# logger.net
KiCad netlist of a schematic drawn in EAGLE
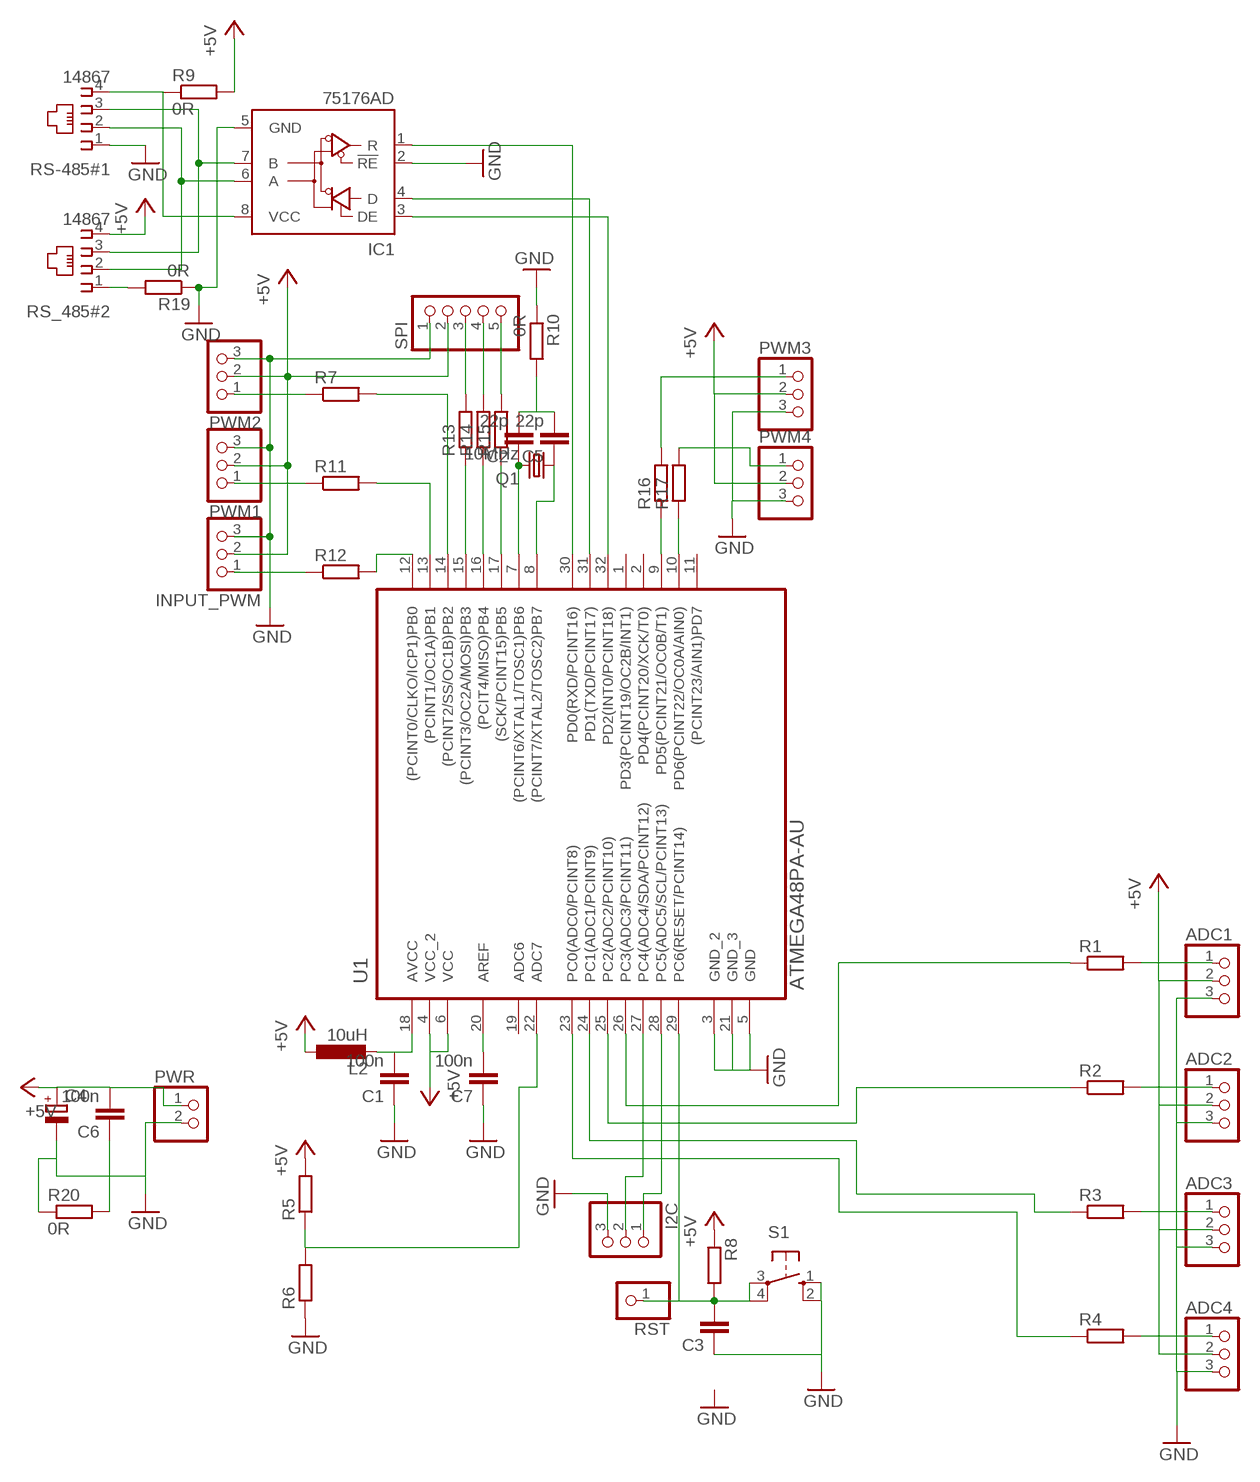
[diagram p0: schematic, sheet 1]

(export (version "E")
  (design (tool "Eeschema 10.0.6"))
  (components
    (comp (ref "ADC1")
      (value "PINHD-1X3")
      (footprint "eagle-import:1X03")
      (libsource (lib "eagle-import") (part "PINHD-1X3"))
    )
    (comp (ref "ADC2")
      (value "PINHD-1X3")
      (footprint "eagle-import:1X03")
      (libsource (lib "eagle-import") (part "PINHD-1X3"))
    )
    (comp (ref "ADC3")
      (value "PINHD-1X3")
      (footprint "eagle-import:1X03")
      (libsource (lib "eagle-import") (part "PINHD-1X3"))
    )
    (comp (ref "ADC4")
      (value "PINHD-1X3")
      (footprint "eagle-import:1X03")
      (libsource (lib "eagle-import") (part "PINHD-1X3"))
    )
    (comp (ref "C1")
      (value "100n")
      (footprint "eagle-import:C0805")
      (libsource (lib "eagle-import") (part "C-EUC0805"))
    )
    (comp (ref "C2")
      (value "22p")
      (footprint "eagle-import:C0805")
      (libsource (lib "eagle-import") (part "C-EUC0805"))
    )
    (comp (ref "C3")
      (value "C-EUC0805")
      (footprint "eagle-import:C0805")
      (libsource (lib "eagle-import") (part "C-EUC0805"))
    )
    (comp (ref "C4")
      (value "CPOL-EUE2,5-6E")
      (footprint "eagle-import:E2,5-6E")
      (libsource (lib "eagle-import") (part "CPOL-EUE2,5-6E"))
    )
    (comp (ref "C5")
      (value "22p")
      (footprint "eagle-import:C0805")
      (libsource (lib "eagle-import") (part "C-EUC0805"))
    )
    (comp (ref "C6")
      (value "100n")
      (footprint "eagle-import:C0805")
      (libsource (lib "eagle-import") (part "C-EUC0805"))
    )
    (comp (ref "C7")
      (value "100n")
      (footprint "eagle-import:C0805")
      (libsource (lib "eagle-import") (part "C-EUC0805"))
    )
    (comp (ref "I2C")
      (value "PINHD-1X3")
      (footprint "eagle-import:1X03")
      (libsource (lib "eagle-import") (part "PINHD-1X3"))
    )
    (comp (ref "IC1")
      (value "75176AD")
      (footprint "eagle-import:D_R-PDSO-G8")
      (libsource (lib "eagle-import") (part "75176AD"))
    )
    (comp (ref "INPUT_PWM")
      (value "PINHD-1X3")
      (footprint "eagle-import:1X03")
      (libsource (lib "eagle-import") (part "PINHD-1X3"))
    )
    (comp (ref "L2")
      (value "10uH")
      (footprint "eagle-import:L1206")
      (libsource (lib "eagle-import") (part "L-EU"))
    )
    (comp (ref "PWM1")
      (value "PINHD-1X3")
      (footprint "eagle-import:1X03")
      (libsource (lib "eagle-import") (part "PINHD-1X3"))
    )
    (comp (ref "PWM2")
      (value "PINHD-1X3")
      (footprint "eagle-import:1X03")
      (libsource (lib "eagle-import") (part "PINHD-1X3"))
    )
    (comp (ref "PWM3")
      (value "PINHD-1X3")
      (footprint "eagle-import:1X03")
      (libsource (lib "eagle-import") (part "PINHD-1X3"))
    )
    (comp (ref "PWM4")
      (value "PINHD-1X3")
      (footprint "eagle-import:1X03")
      (libsource (lib "eagle-import") (part "PINHD-1X3"))
    )
    (comp (ref "PWR")
      (value "PINHD-1X2")
      (footprint "eagle-import:1X02")
      (libsource (lib "eagle-import") (part "PINHD-1X2"))
    )
    (comp (ref "Q1")
      (value "10MHz")
      (footprint "eagle-import:HC49U-V")
      (libsource (lib "eagle-import") (part "CRYSTALHC49U-V"))
    )
    (comp (ref "R1")
      (value "R-EU_R0805")
      (footprint "eagle-import:R0805")
      (libsource (lib "eagle-import") (part "R-EU_R0805"))
    )
    (comp (ref "R2")
      (value "R-EU_R0805")
      (footprint "eagle-import:R0805")
      (libsource (lib "eagle-import") (part "R-EU_R0805"))
    )
    (comp (ref "R3")
      (value "R-EU_R0805")
      (footprint "eagle-import:R0805")
      (libsource (lib "eagle-import") (part "R-EU_R0805"))
    )
    (comp (ref "R4")
      (value "R-EU_R0805")
      (footprint "eagle-import:R0805")
      (libsource (lib "eagle-import") (part "R-EU_R0805"))
    )
    (comp (ref "R5")
      (value "R-EU_R0805")
      (footprint "eagle-import:R0805")
      (libsource (lib "eagle-import") (part "R-EU_R0805"))
    )
    (comp (ref "R6")
      (value "R-EU_R1206")
      (footprint "eagle-import:R1206")
      (libsource (lib "eagle-import") (part "R-EU_R1206"))
    )
    (comp (ref "R7")
      (value "R-EU_R0805")
      (footprint "eagle-import:R0805")
      (libsource (lib "eagle-import") (part "R-EU_R0805"))
    )
    (comp (ref "R8")
      (value "R-EU_R0805")
      (footprint "eagle-import:R0805")
      (libsource (lib "eagle-import") (part "R-EU_R0805"))
    )
    (comp (ref "R9")
      (value "0R")
      (footprint "eagle-import:R1206")
      (libsource (lib "eagle-import") (part "R-EU_R1206"))
    )
    (comp (ref "R10")
      (value "0R")
      (footprint "eagle-import:R1206")
      (libsource (lib "eagle-import") (part "R-EU_R1206"))
    )
    (comp (ref "R11")
      (value "R-EU_R0805")
      (footprint "eagle-import:R0805")
      (libsource (lib "eagle-import") (part "R-EU_R0805"))
    )
    (comp (ref "R12")
      (value "R-EU_R0805")
      (footprint "eagle-import:R0805")
      (libsource (lib "eagle-import") (part "R-EU_R0805"))
    )
    (comp (ref "R13")
      (value "R-EU_R0805")
      (footprint "eagle-import:R0805")
      (libsource (lib "eagle-import") (part "R-EU_R0805"))
    )
    (comp (ref "R14")
      (value "R-EU_R0805")
      (footprint "eagle-import:R0805")
      (libsource (lib "eagle-import") (part "R-EU_R0805"))
    )
    (comp (ref "R15")
      (value "R-EU_R0805")
      (footprint "eagle-import:R0805")
      (libsource (lib "eagle-import") (part "R-EU_R0805"))
    )
    (comp (ref "R16")
      (value "R-EU_R0805")
      (footprint "eagle-import:R0805")
      (libsource (lib "eagle-import") (part "R-EU_R0805"))
    )
    (comp (ref "R17")
      (value "R-EU_R0805")
      (footprint "eagle-import:R0805")
      (libsource (lib "eagle-import") (part "R-EU_R0805"))
    )
    (comp (ref "R19")
      (value "0R")
      (footprint "eagle-import:R1206")
      (libsource (lib "eagle-import") (part "R-EU_R1206"))
    )
    (comp (ref "R20")
      (value "0R")
      (footprint "eagle-import:R1206")
      (libsource (lib "eagle-import") (part "R-EU_R1206"))
    )
    (comp (ref "RS-485#1")
      (value "14867")
      (footprint "eagle-import:14867")
      (libsource (lib "eagle-import") (part "14867"))
    )
    (comp (ref "RST")
      (value "PINHD-1X1")
      (footprint "eagle-import:1X01")
      (libsource (lib "eagle-import") (part "PINHD-1X1"))
    )
    (comp (ref "RS_485#2")
      (value "14867")
      (footprint "eagle-import:14867")
      (libsource (lib "eagle-import") (part "14867"))
    )
    (comp (ref "S1")
      (value "10-XX")
      (footprint "eagle-import:B3F-10XX")
      (fields (field (name "MPN") "B3F-1000"))
      (libsource (lib "eagle-import") (part "10-XX"))
    )
    (comp (ref "SPI")
      (value "PINHD-1X5")
      (footprint "eagle-import:1X05")
      (libsource (lib "eagle-import") (part "PINHD-1X5"))
    )
    (comp (ref "U1")
      (value "ATMEGA48PA-AU")
      (footprint "eagle-import:QFP80P900X900X120-32N")
      (libsource (lib "eagle-import") (part "ATMEGA48PA-AU"))
    )
  )
  (nets
    (net (code "1") (name "+5V") (class "Default")
      (node (ref "ADC1") (pin "2") (pinfunction "2_2") (pintype "passive"))
      (node (ref "ADC2") (pin "2") (pinfunction "2_2") (pintype "passive"))
      (node (ref "ADC3") (pin "2") (pinfunction "2_2") (pintype "passive"))
      (node (ref "ADC4") (pin "2") (pinfunction "2_2") (pintype "passive"))
      (node (ref "C4") (pin "+") (pinfunction "+_+") (pintype "passive"))
      (node (ref "C6") (pin "2") (pinfunction "2_2") (pintype "passive"))
      (node (ref "INPUT_PWM") (pin "2") (pinfunction "2_2") (pintype "passive"))
      (node (ref "L2") (pin "1") (pinfunction "1_1") (pintype "passive"))
      (node (ref "PWM1") (pin "2") (pinfunction "2_2") (pintype "passive"))
      (node (ref "PWM2") (pin "2") (pinfunction "2_2") (pintype "passive"))
      (node (ref "PWM3") (pin "2") (pinfunction "2_2") (pintype "passive"))
      (node (ref "PWM4") (pin "2") (pinfunction "2_2") (pintype "passive"))
      (node (ref "PWR") (pin "1") (pinfunction "1_1") (pintype "passive"))
      (node (ref "R5") (pin "2") (pinfunction "2_2") (pintype "passive"))
      (node (ref "R8") (pin "1") (pinfunction "1_1") (pintype "passive"))
      (node (ref "R9") (pin "2") (pinfunction "2_2") (pintype "passive"))
      (node (ref "RS_485#2") (pin "4") (pinfunction "4_4") (pintype "passive"))
      (node (ref "SPI") (pin "2") (pinfunction "2_2") (pintype "passive"))
      (node (ref "U1") (pin "4") (pinfunction "VCC_2_4") (pintype "power_in"))
      (node (ref "U1") (pin "6") (pinfunction "VCC_6") (pintype "power_in"))
    )
    (net (code "2") (name "GND") (class "Default")
      (node (ref "ADC1") (pin "3") (pinfunction "3_3") (pintype "passive"))
      (node (ref "ADC2") (pin "3") (pinfunction "3_3") (pintype "passive"))
      (node (ref "ADC3") (pin "3") (pinfunction "3_3") (pintype "passive"))
      (node (ref "ADC4") (pin "3") (pinfunction "3_3") (pintype "passive"))
      (node (ref "C1") (pin "1") (pinfunction "1_1") (pintype "passive"))
      (node (ref "C3") (pin "1") (pinfunction "1_1") (pintype "passive"))
      (node (ref "C4") (pin "-") (pinfunction "-_-") (pintype "passive"))
      (node (ref "C6") (pin "1") (pinfunction "1_1") (pintype "passive"))
      (node (ref "C7") (pin "1") (pinfunction "1_1") (pintype "passive"))
      (node (ref "I2C") (pin "3") (pinfunction "3_3") (pintype "passive"))
      (node (ref "IC1") (pin "2") (pinfunction "~{RE}_2") (pintype "input"))
      (node (ref "IC1") (pin "5") (pinfunction "GND_5") (pintype "power_in"))
      (node (ref "INPUT_PWM") (pin "3") (pinfunction "3_3") (pintype "passive"))
      (node (ref "PWM1") (pin "3") (pinfunction "3_3") (pintype "passive"))
      (node (ref "PWM2") (pin "3") (pinfunction "3_3") (pintype "passive"))
      (node (ref "PWM3") (pin "3") (pinfunction "3_3") (pintype "passive"))
      (node (ref "PWM4") (pin "3") (pinfunction "3_3") (pintype "passive"))
      (node (ref "PWR") (pin "2") (pinfunction "2_2") (pintype "passive"))
      (node (ref "R10") (pin "1") (pinfunction "1_1") (pintype "passive"))
      (node (ref "R19") (pin "1") (pinfunction "1_1") (pintype "passive"))
      (node (ref "R20") (pin "1") (pinfunction "1_1") (pintype "passive"))
      (node (ref "R20") (pin "2") (pinfunction "2_2") (pintype "passive"))
      (node (ref "R6") (pin "1") (pinfunction "1_1") (pintype "passive"))
      (node (ref "RS-485#1") (pin "1") (pinfunction "1_1") (pintype "passive"))
      (node (ref "S1") (pin "1") (pinfunction "S_1") (pintype "passive"))
      (node (ref "S1") (pin "2") (pinfunction "S1_2") (pintype "passive"))
      (node (ref "SPI") (pin "1") (pinfunction "1_1") (pintype "passive"))
      (node (ref "U1") (pin "21") (pinfunction "GND_3_21") (pintype "passive"))
      (node (ref "U1") (pin "3") (pinfunction "GND_2_3") (pintype "passive"))
      (node (ref "U1") (pin "5") (pinfunction "GND_5") (pintype "passive"))
    )
    (net (code "3") (name "Net-(ADC1-Pad1)") (class "Default")
      (node (ref "ADC1") (pin "1") (pinfunction "1_1") (pintype "passive"))
      (node (ref "R1") (pin "2") (pinfunction "2_2") (pintype "passive"))
    )
    (net (code "4") (name "Net-(ADC2-Pad1)") (class "Default")
      (node (ref "ADC2") (pin "1") (pinfunction "1_1") (pintype "passive"))
      (node (ref "R2") (pin "2") (pinfunction "2_2") (pintype "passive"))
    )
    (net (code "5") (name "Net-(ADC3-Pad1)") (class "Default")
      (node (ref "ADC3") (pin "1") (pinfunction "1_1") (pintype "passive"))
      (node (ref "R3") (pin "2") (pinfunction "2_2") (pintype "passive"))
    )
    (net (code "6") (name "Net-(ADC4-Pad1)") (class "Default")
      (node (ref "ADC4") (pin "1") (pinfunction "1_1") (pintype "passive"))
      (node (ref "R4") (pin "2") (pinfunction "2_2") (pintype "passive"))
    )
    (net (code "7") (name "Net-(C2-Pad2)") (class "Default")
      (node (ref "C2") (pin "2") (pinfunction "2_2") (pintype "passive"))
      (node (ref "C5") (pin "2") (pinfunction "2_2") (pintype "passive"))
      (node (ref "R10") (pin "2") (pinfunction "2_2") (pintype "passive"))
    )
    (net (code "8") (name "Net-(IC1-A)") (class "Default")
      (node (ref "IC1") (pin "6") (pinfunction "A_6") (pintype "output"))
      (node (ref "RS-485#1") (pin "2") (pinfunction "2_2") (pintype "passive"))
      (node (ref "RS_485#2") (pin "2") (pinfunction "2_2") (pintype "passive"))
    )
    (net (code "9") (name "Net-(IC1-B)") (class "Default")
      (node (ref "IC1") (pin "7") (pinfunction "B_7") (pintype "output"))
      (node (ref "RS-485#1") (pin "3") (pinfunction "3_3") (pintype "passive"))
      (node (ref "RS_485#2") (pin "3") (pinfunction "3_3") (pintype "passive"))
    )
    (net (code "10") (name "Net-(IC1-D)") (class "Default")
      (node (ref "IC1") (pin "4") (pinfunction "D_4") (pintype "input"))
      (node (ref "U1") (pin "31") (pinfunction "PD1(TXD/PCINT17)_31") (pintype "bidirectional"))
    )
    (net (code "11") (name "Net-(IC1-DE)") (class "Default")
      (node (ref "IC1") (pin "3") (pinfunction "DE_3") (pintype "input"))
      (node (ref "U1") (pin "32") (pinfunction "PD2(INT0/PCINT18)_32") (pintype "bidirectional"))
    )
    (net (code "12") (name "Net-(IC1-R)") (class "Default")
      (node (ref "IC1") (pin "1") (pinfunction "R_1") (pintype "input"))
      (node (ref "U1") (pin "30") (pinfunction "PD0(RXD/PCINT16)_30") (pintype "bidirectional"))
    )
    (net (code "13") (name "Net-(IC1-VCC)") (class "Default")
      (node (ref "IC1") (pin "8") (pinfunction "VCC_8") (pintype "power_in"))
      (node (ref "R9") (pin "1") (pinfunction "1_1") (pintype "passive"))
      (node (ref "RS-485#1") (pin "4") (pinfunction "4_4") (pintype "passive"))
    )
    (net (code "14") (name "Net-(INPUT_PWM-Pad1)") (class "Default")
      (node (ref "INPUT_PWM") (pin "1") (pinfunction "1_1") (pintype "passive"))
      (node (ref "R12") (pin "1") (pinfunction "1_1") (pintype "passive"))
    )
    (net (code "15") (name "Net-(PWM1-Pad1)") (class "Default")
      (node (ref "PWM1") (pin "1") (pinfunction "1_1") (pintype "passive"))
      (node (ref "R11") (pin "1") (pinfunction "1_1") (pintype "passive"))
    )
    (net (code "16") (name "Net-(PWM2-Pad1)") (class "Default")
      (node (ref "PWM2") (pin "1") (pinfunction "1_1") (pintype "passive"))
      (node (ref "R7") (pin "1") (pinfunction "1_1") (pintype "passive"))
    )
    (net (code "17") (name "Net-(PWM3-Pad1)") (class "Default")
      (node (ref "PWM3") (pin "1") (pinfunction "1_1") (pintype "passive"))
      (node (ref "R16") (pin "2") (pinfunction "2_2") (pintype "passive"))
    )
    (net (code "18") (name "Net-(PWM4-Pad1)") (class "Default")
      (node (ref "PWM4") (pin "1") (pinfunction "1_1") (pintype "passive"))
      (node (ref "R17") (pin "2") (pinfunction "2_2") (pintype "passive"))
    )
    (net (code "19") (name "Net-(R13-Pad2)") (class "Default")
      (node (ref "R13") (pin "2") (pinfunction "2_2") (pintype "passive"))
      (node (ref "SPI") (pin "3") (pinfunction "3_3") (pintype "passive"))
    )
    (net (code "20") (name "Net-(R14-Pad2)") (class "Default")
      (node (ref "R14") (pin "2") (pinfunction "2_2") (pintype "passive"))
      (node (ref "SPI") (pin "4") (pinfunction "4_4") (pintype "passive"))
    )
    (net (code "21") (name "Net-(R15-Pad2)") (class "Default")
      (node (ref "R15") (pin "2") (pinfunction "2_2") (pintype "passive"))
      (node (ref "SPI") (pin "5") (pinfunction "5_5") (pintype "passive"))
    )
    (net (code "22") (name "Net-(R19-Pad2)") (class "Default")
      (node (ref "R19") (pin "2") (pinfunction "2_2") (pintype "passive"))
      (node (ref "RS_485#2") (pin "1") (pinfunction "1_1") (pintype "passive"))
    )
    (net (code "23") (name "Net-(S1-P)") (class "Default")
      (node (ref "C3") (pin "2") (pinfunction "2_2") (pintype "passive"))
      (node (ref "R8") (pin "2") (pinfunction "2_2") (pintype "passive"))
      (node (ref "RST") (pin "1") (pinfunction "1_1") (pintype "passive"))
      (node (ref "S1") (pin "3") (pinfunction "P_3") (pintype "passive"))
      (node (ref "S1") (pin "4") (pinfunction "P1_4") (pintype "passive"))
      (node (ref "U1") (pin "29") (pinfunction "PC6(RESET/PCINT14)_29") (pintype "bidirectional"))
    )
    (net (code "24") (name "Net-(U1-(PCINT0{slash}CLKO{slash}ICP1)PB0)") (class "Default")
      (node (ref "R12") (pin "2") (pinfunction "2_2") (pintype "passive"))
      (node (ref "U1") (pin "12") (pinfunction "(PCINT0/CLKO/ICP1)PB0_12") (pintype "bidirectional"))
    )
    (net (code "25") (name "Net-(U1-(PCINT1{slash}OC1A)PB1)") (class "Default")
      (node (ref "R11") (pin "2") (pinfunction "2_2") (pintype "passive"))
      (node (ref "U1") (pin "13") (pinfunction "(PCINT1/OC1A)PB1_13") (pintype "bidirectional"))
    )
    (net (code "26") (name "Net-(U1-(PCINT2{slash}SS{slash}OC1B)PB2)") (class "Default")
      (node (ref "R7") (pin "2") (pinfunction "2_2") (pintype "passive"))
      (node (ref "U1") (pin "14") (pinfunction "(PCINT2/SS/OC1B)PB2_14") (pintype "bidirectional"))
    )
    (net (code "27") (name "Net-(U1-(PCINT3{slash}OC2A{slash}MOSI)PB3)") (class "Default")
      (node (ref "R13") (pin "1") (pinfunction "1_1") (pintype "passive"))
      (node (ref "U1") (pin "15") (pinfunction "(PCINT3/OC2A/MOSI)PB3_15") (pintype "bidirectional"))
    )
    (net (code "28") (name "Net-(U1-(PCINT6{slash}XTAL1{slash}TOSC1)PB6)") (class "Default")
      (node (ref "C2") (pin "1") (pinfunction "1_1") (pintype "passive"))
      (node (ref "Q1") (pin "2") (pinfunction "2_2") (pintype "passive"))
      (node (ref "U1") (pin "7") (pinfunction "(PCINT6/XTAL1/TOSC1)PB6_7") (pintype "bidirectional"))
    )
    (net (code "29") (name "Net-(U1-(PCINT7{slash}XTAL2{slash}TOSC2)PB7)") (class "Default")
      (node (ref "C5") (pin "1") (pinfunction "1_1") (pintype "passive"))
      (node (ref "Q1") (pin "1") (pinfunction "1_1") (pintype "passive"))
      (node (ref "U1") (pin "8") (pinfunction "(PCINT7/XTAL2/TOSC2)PB7_8") (pintype "bidirectional"))
    )
    (net (code "30") (name "Net-(U1-(PCIT4{slash}MISO)PB4)") (class "Default")
      (node (ref "R14") (pin "1") (pinfunction "1_1") (pintype "passive"))
      (node (ref "U1") (pin "16") (pinfunction "(PCIT4/MISO)PB4_16") (pintype "bidirectional"))
    )
    (net (code "31") (name "Net-(U1-(SCK{slash}PCINT15)PB5)") (class "Default")
      (node (ref "R15") (pin "1") (pinfunction "1_1") (pintype "passive"))
      (node (ref "U1") (pin "17") (pinfunction "(SCK/PCINT15)PB5_17") (pintype "bidirectional"))
    )
    (net (code "32") (name "Net-(U1-ADC7)") (class "Default")
      (node (ref "R5") (pin "1") (pinfunction "1_1") (pintype "passive"))
      (node (ref "R6") (pin "2") (pinfunction "2_2") (pintype "passive"))
      (node (ref "U1") (pin "22") (pinfunction "ADC7_22") (pintype "input"))
    )
    (net (code "33") (name "Net-(U1-AREF)") (class "Default")
      (node (ref "C7") (pin "2") (pinfunction "2_2") (pintype "passive"))
      (node (ref "U1") (pin "20") (pinfunction "AREF_20") (pintype "input"))
    )
    (net (code "34") (name "Net-(U1-AVCC)") (class "Default")
      (node (ref "C1") (pin "2") (pinfunction "2_2") (pintype "passive"))
      (node (ref "L2") (pin "2") (pinfunction "2_2") (pintype "passive"))
      (node (ref "U1") (pin "18") (pinfunction "AVCC_18") (pintype "power_in"))
    )
    (net (code "35") (name "Net-(U1-PC0(ADC0{slash}PCINT8))") (class "Default")
      (node (ref "R4") (pin "1") (pinfunction "1_1") (pintype "passive"))
      (node (ref "U1") (pin "23") (pinfunction "PC0(ADC0/PCINT8)_23") (pintype "bidirectional"))
    )
    (net (code "36") (name "Net-(U1-PC1(ADC1{slash}PCINT9))") (class "Default")
      (node (ref "R3") (pin "1") (pinfunction "1_1") (pintype "passive"))
      (node (ref "U1") (pin "24") (pinfunction "PC1(ADC1/PCINT9)_24") (pintype "bidirectional"))
    )
    (net (code "37") (name "Net-(U1-PC2(ADC2{slash}PCINT10))") (class "Default")
      (node (ref "R2") (pin "1") (pinfunction "1_1") (pintype "passive"))
      (node (ref "U1") (pin "25") (pinfunction "PC2(ADC2/PCINT10)_25") (pintype "bidirectional"))
    )
    (net (code "38") (name "Net-(U1-PC3(ADC3{slash}PCINT11))") (class "Default")
      (node (ref "R1") (pin "1") (pinfunction "1_1") (pintype "passive"))
      (node (ref "U1") (pin "26") (pinfunction "PC3(ADC3/PCINT11)_26") (pintype "bidirectional"))
    )
    (net (code "39") (name "Net-(U1-PC4(ADC4{slash}SDA{slash}PCINT12))") (class "Default")
      (node (ref "I2C") (pin "2") (pinfunction "2_2") (pintype "passive"))
      (node (ref "U1") (pin "27") (pinfunction "PC4(ADC4/SDA/PCINT12)_27") (pintype "bidirectional"))
    )
    (net (code "40") (name "Net-(U1-PC5(ADC5{slash}SCL{slash}PCINT13))") (class "Default")
      (node (ref "I2C") (pin "1") (pinfunction "1_1") (pintype "passive"))
      (node (ref "U1") (pin "28") (pinfunction "PC5(ADC5/SCL/PCINT13)_28") (pintype "bidirectional"))
    )
    (net (code "41") (name "Net-(U1-PD5(PCINT21{slash}OC0B{slash}T1))") (class "Default")
      (node (ref "R16") (pin "1") (pinfunction "1_1") (pintype "passive"))
      (node (ref "U1") (pin "9") (pinfunction "PD5(PCINT21/OC0B/T1)_9") (pintype "bidirectional"))
    )
    (net (code "42") (name "Net-(U1-PD6(PCINT22{slash}OC0A{slash}AIN0))") (class "Default")
      (node (ref "R17") (pin "1") (pinfunction "1_1") (pintype "passive"))
      (node (ref "U1") (pin "10") (pinfunction "PD6(PCINT22/OC0A/AIN0)_10") (pintype "bidirectional"))
    )
    (net (code "43") (name "unconnected-(U1-(PCINT23{slash}AIN1)PD7-Pad11)") (class "Default")
      (node (ref "U1") (pin "11") (pinfunction "(PCINT23/AIN1)PD7_11") (pintype "bidirectional"))
    )
    (net (code "44") (name "unconnected-(U1-ADC6-Pad19)") (class "Default")
      (node (ref "U1") (pin "19") (pinfunction "ADC6_19") (pintype "input"))
    )
    (net (code "45") (name "unconnected-(U1-PD3(PCINT19{slash}OC2B{slash}INT1)-Pad1)") (class "Default")
      (node (ref "U1") (pin "1") (pinfunction "PD3(PCINT19/OC2B/INT1)_1") (pintype "bidirectional"))
    )
    (net (code "46") (name "unconnected-(U1-PD4(PCINT20{slash}XCK{slash}T0)-Pad2)") (class "Default")
      (node (ref "U1") (pin "2") (pinfunction "PD4(PCINT20/XCK/T0)_2") (pintype "bidirectional"))
    )
  )
)
